# 0_2.net
KiCad netlist of a schematic drawn in Altium Designer
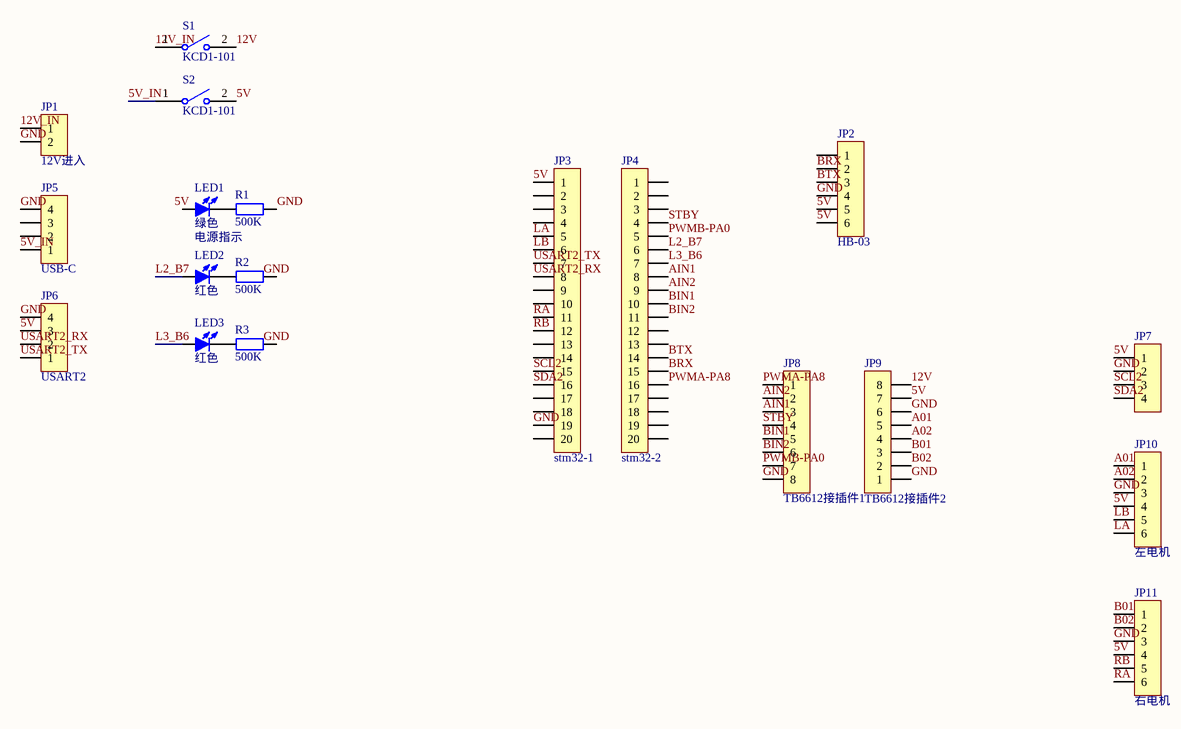
[diagram p0: 0.2.SchDoc]

(export (version "E")
  (design (tool "Eeschema 10.0.6"))
  (components
    (comp (ref "JP1")
      (value "HDR-1X2")
      (footprint "KF2EDGK5.08-LI-2P")
      (description "2P接插件")
      (fields (field (name "BOM名称") "12V进入") (field (name "版权归属") "源创客"))
      (libsource (lib "5.8 - 接插件-脚距5.08 (200mil) ") (part "Header 2"))
    )
    (comp (ref "JP2")
      (value "HDR-1X6")
      (footprint "HDR2.54-M-LI-6P")
      (description "6P接插件")
      (fields (field (name "BOM名称") "HB-03") (field (name "版权归属") "封装库来自淘宝 ID：黄晶宝石"))
      (libsource (lib "5.3 - 接插件-脚距2.54 (100mil) ") (part "Header 6"))
    )
    (comp (ref "JP3")
      (value "HDR-1X20")
      (footprint "HDR2.54-M-LI-20P")
      (description "20P接插件")
      (fields (field (name "BOM名称") "stm32-1") (field (name "版权归属") "封装库来自淘宝 ID：黄晶宝石"))
      (libsource (lib "5.3 - 接插件-脚距2.54 (100mil) ") (part "Header 20"))
    )
    (comp (ref "JP4")
      (value "HDR-1X20")
      (footprint "HDR2.54-M-LI-20P")
      (description "20P接插件")
      (fields (field (name "BOM名称") "stm32-2") (field (name "版权归属") "封装库来自淘宝 ID：黄晶宝石"))
      (libsource (lib "") (part "Header 20_1"))
    )
    (comp (ref "JP5")
      (value "HDR-1X4")
      (footprint "HDR2.54-M-LI-4P")
      (description "4P接插件")
      (fields (field (name "BOM名称") "USB-C") (field (name "版权归属") "封装库来自淘宝 ID：黄晶宝石"))
      (libsource (lib "5.3 - 接插件-脚距2.54 (100mil) ") (part "Header 4"))
    )
    (comp (ref "JP6")
      (value "HDR-1X4")
      (footprint "HDR2.54-M-LI-4P")
      (description "4P接插件")
      (fields (field (name "BOM名称") "USART2") (field (name "版权归属") "封装库来自淘宝 ID：黄晶宝石"))
      (libsource (lib "5.3 - 接插件-脚距2.54 (100mil) ") (part "Header 4"))
    )
    (comp (ref "JP7")
      (value "HDR-1X4")
      (footprint "XH2.54-WI-4P")
      (description "4P接插件")
      (fields (field (name "版权归属") "封装库来自淘宝 ID：黄晶宝石"))
      (libsource (lib "") (part "Header 4_1"))
    )
    (comp (ref "JP8")
      (value "HDR-1X8")
      (footprint "HDR2.54-M-LI-8P")
      (description "8P接插件")
      (fields (field (name "BOM名称") "TB6612接插件1") (field (name "版权归属") "封装库来自淘宝 ID：黄晶宝石"))
      (libsource (lib "") (part "Header 8_1"))
    )
    (comp (ref "JP9")
      (value "HDR-1X8")
      (footprint "HDR2.54-M-LI-8P")
      (description "8P接插件")
      (fields (field (name "BOM名称") "TB6612接插件2") (field (name "版权归属") "封装库来自淘宝 ID：黄晶宝石"))
      (libsource (lib "5.3 - 接插件-脚距2.54 (100mil) ") (part "Header 8"))
    )
    (comp (ref "JP10")
      (value "HDR-1X6")
      (footprint "KF128-5.08-6P")
      (description "6P接插件")
      (fields (field (name "BOM名称") "左电机") (field (name "版权归属") "源创客"))
      (libsource (lib "5.8 - 接插件-脚距5.08 (200mil) ") (part "Header 6"))
    )
    (comp (ref "JP11")
      (value "HDR-1X6")
      (footprint "KF128-5.08-6P")
      (description "6P接插件")
      (fields (field (name "BOM名称") "右电机") (field (name "版权归属") "源创客"))
      (libsource (lib "5.8 - 接插件-脚距5.08 (200mil) ") (part "Header 6"))
    )
    (comp (ref "LED1")
      (value "绿色")
      (footprint "LED 0805G")
      (description "贴片LED")
      (fields (field (name "BOM名称") "电源指示") (field (name "版权归属") "源创客"))
      (libsource (lib "LED") (part "LED-SMD"))
    )
    (comp (ref "LED2")
      (value "红色")
      (footprint "LED 0805G")
      (description "贴片LED")
      (fields (field (name "版权归属") "源创客"))
      (libsource (lib "LED") (part "LED-SMD"))
    )
    (comp (ref "LED3")
      (value "红色")
      (footprint "LED 0805G")
      (description "贴片LED")
      (fields (field (name "版权归属") "源创客"))
      (libsource (lib "LED") (part "LED-SMD"))
    )
    (comp (ref "R1")
      (value "500K")
      (footprint "R 0805_M")
      (description "贴片电阻")
      (fields (field (name "版权归属") "来自淘宝 ID：黄晶宝石"))
      (libsource (lib "0.1 - 电阻-电容-电感") (part "R"))
    )
    (comp (ref "R2")
      (value "500K")
      (footprint "R 0805_M")
      (description "贴片电阻")
      (fields (field (name "版权归属") "来自淘宝 ID：黄晶宝石"))
      (libsource (lib "0.1 - 电阻-电容-电感") (part "R"))
    )
    (comp (ref "R3")
      (value "500K")
      (footprint "R 0805_M")
      (description "贴片电阻")
      (fields (field (name "版权归属") "来自淘宝 ID：黄晶宝石"))
      (libsource (lib "0.1 - 电阻-电容-电感") (part "R"))
    )
    (comp (ref "S1")
      (value "KCD1-101")
      (footprint "KCD1-101")
      (description "1路单刀船型开关")
      (fields (field (name "版权归属") "封装库来自淘宝 ID：黄晶宝石"))
      (libsource (lib "0.7 - 常用按键-开关") (part "KCD1-101"))
    )
    (comp (ref "S2")
      (value "KCD1-101")
      (footprint "KCD1-101")
      (description "1路单刀船型开关")
      (fields (field (name "版权归属") "封装库来自淘宝 ID：黄晶宝石"))
      (libsource (lib "0.7 - 常用按键-开关") (part "KCD1-101"))
    )
  )
  (nets
    (net (code "1") (name "/5V") (class "Default")
      (node (ref "JP10") (pin "4") (pinfunction "4_4") (pintype "passive"))
      (node (ref "JP11") (pin "4") (pinfunction "4_4") (pintype "passive"))
      (node (ref "JP2") (pin "5") (pinfunction "5_5") (pintype "passive"))
      (node (ref "JP2") (pin "6") (pinfunction "6_6") (pintype "passive"))
      (node (ref "JP3") (pin "1") (pinfunction "1_1") (pintype "passive"))
      (node (ref "JP6") (pin "3") (pinfunction "3_3") (pintype "passive"))
      (node (ref "JP7") (pin "1") (pinfunction "1_1") (pintype "passive"))
      (node (ref "JP9") (pin "7") (pinfunction "7_7") (pintype "passive"))
      (node (ref "LED1") (pin "1") (pinfunction "A_1") (pintype "passive"))
      (node (ref "S2") (pin "2") (pinfunction "2_2") (pintype "passive"))
    )
    (net (code "2") (name "/5V_IN") (class "Default")
      (node (ref "JP5") (pin "1") (pinfunction "1_1") (pintype "passive"))
      (node (ref "S2") (pin "1") (pinfunction "1_1") (pintype "passive"))
    )
    (net (code "3") (name "/12V") (class "Default")
      (node (ref "JP9") (pin "8") (pinfunction "8_8") (pintype "passive"))
      (node (ref "S1") (pin "2") (pinfunction "2_2") (pintype "passive"))
    )
    (net (code "4") (name "/12V_IN") (class "Default")
      (node (ref "JP1") (pin "1") (pinfunction "1_1") (pintype "passive"))
      (node (ref "S1") (pin "1") (pinfunction "1_1") (pintype "passive"))
    )
    (net (code "5") (name "/A01") (class "Default")
      (node (ref "JP10") (pin "1") (pinfunction "1_1") (pintype "passive"))
      (node (ref "JP9") (pin "5") (pinfunction "5_5") (pintype "passive"))
    )
    (net (code "6") (name "/A02") (class "Default")
      (node (ref "JP10") (pin "2") (pinfunction "2_2") (pintype "passive"))
      (node (ref "JP9") (pin "4") (pinfunction "4_4") (pintype "passive"))
    )
    (net (code "7") (name "/AIN1") (class "Default")
      (node (ref "JP4") (pin "8") (pinfunction "8_8") (pintype "passive"))
      (node (ref "JP8") (pin "3") (pinfunction "3_3") (pintype "passive"))
    )
    (net (code "8") (name "/AIN2") (class "Default")
      (node (ref "JP4") (pin "9") (pinfunction "9_9") (pintype "passive"))
      (node (ref "JP8") (pin "2") (pinfunction "2_2") (pintype "passive"))
    )
    (net (code "9") (name "/B01") (class "Default")
      (node (ref "JP11") (pin "1") (pinfunction "1_1") (pintype "passive"))
      (node (ref "JP9") (pin "3") (pinfunction "3_3") (pintype "passive"))
    )
    (net (code "10") (name "/B02") (class "Default")
      (node (ref "JP11") (pin "2") (pinfunction "2_2") (pintype "passive"))
      (node (ref "JP9") (pin "2") (pinfunction "2_2") (pintype "passive"))
    )
    (net (code "11") (name "/BIN1") (class "Default")
      (node (ref "JP4") (pin "10") (pinfunction "10_10") (pintype "passive"))
      (node (ref "JP8") (pin "5") (pinfunction "5_5") (pintype "passive"))
    )
    (net (code "12") (name "/BIN2") (class "Default")
      (node (ref "JP4") (pin "11") (pinfunction "11_11") (pintype "passive"))
      (node (ref "JP8") (pin "6") (pinfunction "6_6") (pintype "passive"))
    )
    (net (code "13") (name "/BRX") (class "Default")
      (node (ref "JP2") (pin "2") (pinfunction "2_2") (pintype "passive"))
      (node (ref "JP4") (pin "15") (pinfunction "15_15") (pintype "passive"))
    )
    (net (code "14") (name "/BTX") (class "Default")
      (node (ref "JP2") (pin "3") (pinfunction "3_3") (pintype "passive"))
      (node (ref "JP4") (pin "14") (pinfunction "14_14") (pintype "passive"))
    )
    (net (code "15") (name "/GND") (class "Default")
      (node (ref "JP1") (pin "2") (pinfunction "2_2") (pintype "passive"))
      (node (ref "JP10") (pin "3") (pinfunction "3_3") (pintype "passive"))
      (node (ref "JP11") (pin "3") (pinfunction "3_3") (pintype "passive"))
      (node (ref "JP2") (pin "4") (pinfunction "4_4") (pintype "passive"))
      (node (ref "JP3") (pin "19") (pinfunction "19_19") (pintype "passive"))
      (node (ref "JP5") (pin "4") (pinfunction "4_4") (pintype "passive"))
      (node (ref "JP6") (pin "4") (pinfunction "4_4") (pintype "passive"))
      (node (ref "JP7") (pin "2") (pinfunction "2_2") (pintype "passive"))
      (node (ref "JP8") (pin "8") (pinfunction "8_8") (pintype "passive"))
      (node (ref "JP9") (pin "1") (pinfunction "1_1") (pintype "passive"))
      (node (ref "JP9") (pin "6") (pinfunction "6_6") (pintype "passive"))
      (node (ref "R1") (pin "2") (pinfunction "2_2") (pintype "passive"))
      (node (ref "R2") (pin "2") (pinfunction "2_2") (pintype "passive"))
      (node (ref "R3") (pin "2") (pinfunction "2_2") (pintype "passive"))
    )
    (net (code "16") (name "/L2_B7") (class "Default")
      (node (ref "JP4") (pin "6") (pinfunction "6_6") (pintype "passive"))
      (node (ref "LED2") (pin "1") (pinfunction "A_1") (pintype "passive"))
    )
    (net (code "17") (name "/L3_B6") (class "Default")
      (node (ref "JP4") (pin "7") (pinfunction "7_7") (pintype "passive"))
      (node (ref "LED3") (pin "1") (pinfunction "A_1") (pintype "passive"))
    )
    (net (code "18") (name "/LA") (class "Default")
      (node (ref "JP10") (pin "6") (pinfunction "6_6") (pintype "passive"))
      (node (ref "JP3") (pin "5") (pinfunction "5_5") (pintype "passive"))
    )
    (net (code "19") (name "/LB") (class "Default")
      (node (ref "JP10") (pin "5") (pinfunction "5_5") (pintype "passive"))
      (node (ref "JP3") (pin "6") (pinfunction "6_6") (pintype "passive"))
    )
    (net (code "20") (name "/PWMA-PA8") (class "Default")
      (node (ref "JP4") (pin "16") (pinfunction "16_16") (pintype "passive"))
      (node (ref "JP8") (pin "1") (pinfunction "1_1") (pintype "passive"))
    )
    (net (code "21") (name "/PWMB-PA0") (class "Default")
      (node (ref "JP4") (pin "5") (pinfunction "5_5") (pintype "passive"))
      (node (ref "JP8") (pin "7") (pinfunction "7_7") (pintype "passive"))
    )
    (net (code "22") (name "/RA") (class "Default")
      (node (ref "JP11") (pin "6") (pinfunction "6_6") (pintype "passive"))
      (node (ref "JP3") (pin "11") (pinfunction "11_11") (pintype "passive"))
    )
    (net (code "23") (name "/RB") (class "Default")
      (node (ref "JP11") (pin "5") (pinfunction "5_5") (pintype "passive"))
      (node (ref "JP3") (pin "12") (pinfunction "12_12") (pintype "passive"))
    )
    (net (code "24") (name "/SCL2") (class "Default")
      (node (ref "JP3") (pin "15") (pinfunction "15_15") (pintype "passive"))
      (node (ref "JP7") (pin "3") (pinfunction "3_3") (pintype "passive"))
    )
    (net (code "25") (name "/SDA2") (class "Default")
      (node (ref "JP3") (pin "16") (pinfunction "16_16") (pintype "passive"))
      (node (ref "JP7") (pin "4") (pinfunction "4_4") (pintype "passive"))
    )
    (net (code "26") (name "/STBY") (class "Default")
      (node (ref "JP4") (pin "4") (pinfunction "4_4") (pintype "passive"))
      (node (ref "JP8") (pin "4") (pinfunction "4_4") (pintype "passive"))
    )
    (net (code "27") (name "/USART2_RX") (class "Default")
      (node (ref "JP3") (pin "8") (pinfunction "8_8") (pintype "passive"))
      (node (ref "JP6") (pin "2") (pinfunction "2_2") (pintype "passive"))
    )
    (net (code "28") (name "/USART2_TX") (class "Default")
      (node (ref "JP3") (pin "7") (pinfunction "7_7") (pintype "passive"))
      (node (ref "JP6") (pin "1") (pinfunction "1_1") (pintype "passive"))
    )
    (net (code "29") (name "Net-(LED1-K)") (class "Default")
      (node (ref "LED1") (pin "2") (pinfunction "K_2") (pintype "passive"))
      (node (ref "R1") (pin "1") (pinfunction "1_1") (pintype "passive"))
    )
    (net (code "30") (name "Net-(LED2-K)") (class "Default")
      (node (ref "LED2") (pin "2") (pinfunction "K_2") (pintype "passive"))
      (node (ref "R2") (pin "1") (pinfunction "1_1") (pintype "passive"))
    )
    (net (code "31") (name "Net-(LED3-K)") (class "Default")
      (node (ref "LED3") (pin "2") (pinfunction "K_2") (pintype "passive"))
      (node (ref "R3") (pin "1") (pinfunction "1_1") (pintype "passive"))
    )
    (net (code "32") (name "unconnected-(JP2-Pad1)") (class "Default")
      (node (ref "JP2") (pin "1") (pinfunction "1_1") (pintype "passive"))
    )
    (net (code "33") (name "unconnected-(JP3-Pad2)") (class "Default")
      (node (ref "JP3") (pin "2") (pinfunction "2_2") (pintype "passive"))
    )
    (net (code "34") (name "unconnected-(JP3-Pad3)") (class "Default")
      (node (ref "JP3") (pin "3") (pinfunction "3_3") (pintype "passive"))
    )
    (net (code "35") (name "unconnected-(JP3-Pad4)") (class "Default")
      (node (ref "JP3") (pin "4") (pinfunction "4_4") (pintype "passive"))
    )
    (net (code "36") (name "unconnected-(JP3-Pad9)") (class "Default")
      (node (ref "JP3") (pin "9") (pinfunction "9_9") (pintype "passive"))
    )
    (net (code "37") (name "unconnected-(JP3-Pad10)") (class "Default")
      (node (ref "JP3") (pin "10") (pinfunction "10_10") (pintype "passive"))
    )
    (net (code "38") (name "unconnected-(JP3-Pad13)") (class "Default")
      (node (ref "JP3") (pin "13") (pinfunction "13_13") (pintype "passive"))
    )
    (net (code "39") (name "unconnected-(JP3-Pad14)") (class "Default")
      (node (ref "JP3") (pin "14") (pinfunction "14_14") (pintype "passive"))
    )
    (net (code "40") (name "unconnected-(JP3-Pad17)") (class "Default")
      (node (ref "JP3") (pin "17") (pinfunction "17_17") (pintype "passive"))
    )
    (net (code "41") (name "unconnected-(JP3-Pad18)") (class "Default")
      (node (ref "JP3") (pin "18") (pinfunction "18_18") (pintype "passive"))
    )
    (net (code "42") (name "unconnected-(JP3-Pad20)") (class "Default")
      (node (ref "JP3") (pin "20") (pinfunction "20_20") (pintype "passive"))
    )
    (net (code "43") (name "unconnected-(JP4-Pad1)") (class "Default")
      (node (ref "JP4") (pin "1") (pinfunction "1_1") (pintype "passive"))
    )
    (net (code "44") (name "unconnected-(JP4-Pad2)") (class "Default")
      (node (ref "JP4") (pin "2") (pinfunction "2_2") (pintype "passive"))
    )
    (net (code "45") (name "unconnected-(JP4-Pad3)") (class "Default")
      (node (ref "JP4") (pin "3") (pinfunction "3_3") (pintype "passive"))
    )
    (net (code "46") (name "unconnected-(JP4-Pad12)") (class "Default")
      (node (ref "JP4") (pin "12") (pinfunction "12_12") (pintype "passive"))
    )
    (net (code "47") (name "unconnected-(JP4-Pad13)") (class "Default")
      (node (ref "JP4") (pin "13") (pinfunction "13_13") (pintype "passive"))
    )
    (net (code "48") (name "unconnected-(JP4-Pad17)") (class "Default")
      (node (ref "JP4") (pin "17") (pinfunction "17_17") (pintype "passive"))
    )
    (net (code "49") (name "unconnected-(JP4-Pad18)") (class "Default")
      (node (ref "JP4") (pin "18") (pinfunction "18_18") (pintype "passive"))
    )
    (net (code "50") (name "unconnected-(JP4-Pad19)") (class "Default")
      (node (ref "JP4") (pin "19") (pinfunction "19_19") (pintype "passive"))
    )
    (net (code "51") (name "unconnected-(JP4-Pad20)") (class "Default")
      (node (ref "JP4") (pin "20") (pinfunction "20_20") (pintype "passive"))
    )
    (net (code "52") (name "unconnected-(JP5-Pad2)") (class "Default")
      (node (ref "JP5") (pin "2") (pinfunction "2_2") (pintype "passive"))
    )
    (net (code "53") (name "unconnected-(JP5-Pad3)") (class "Default")
      (node (ref "JP5") (pin "3") (pinfunction "3_3") (pintype "passive"))
    )
  )
)
